# Doors_lighting_control.net
KiCad netlist of a schematic drawn in Altium Designer
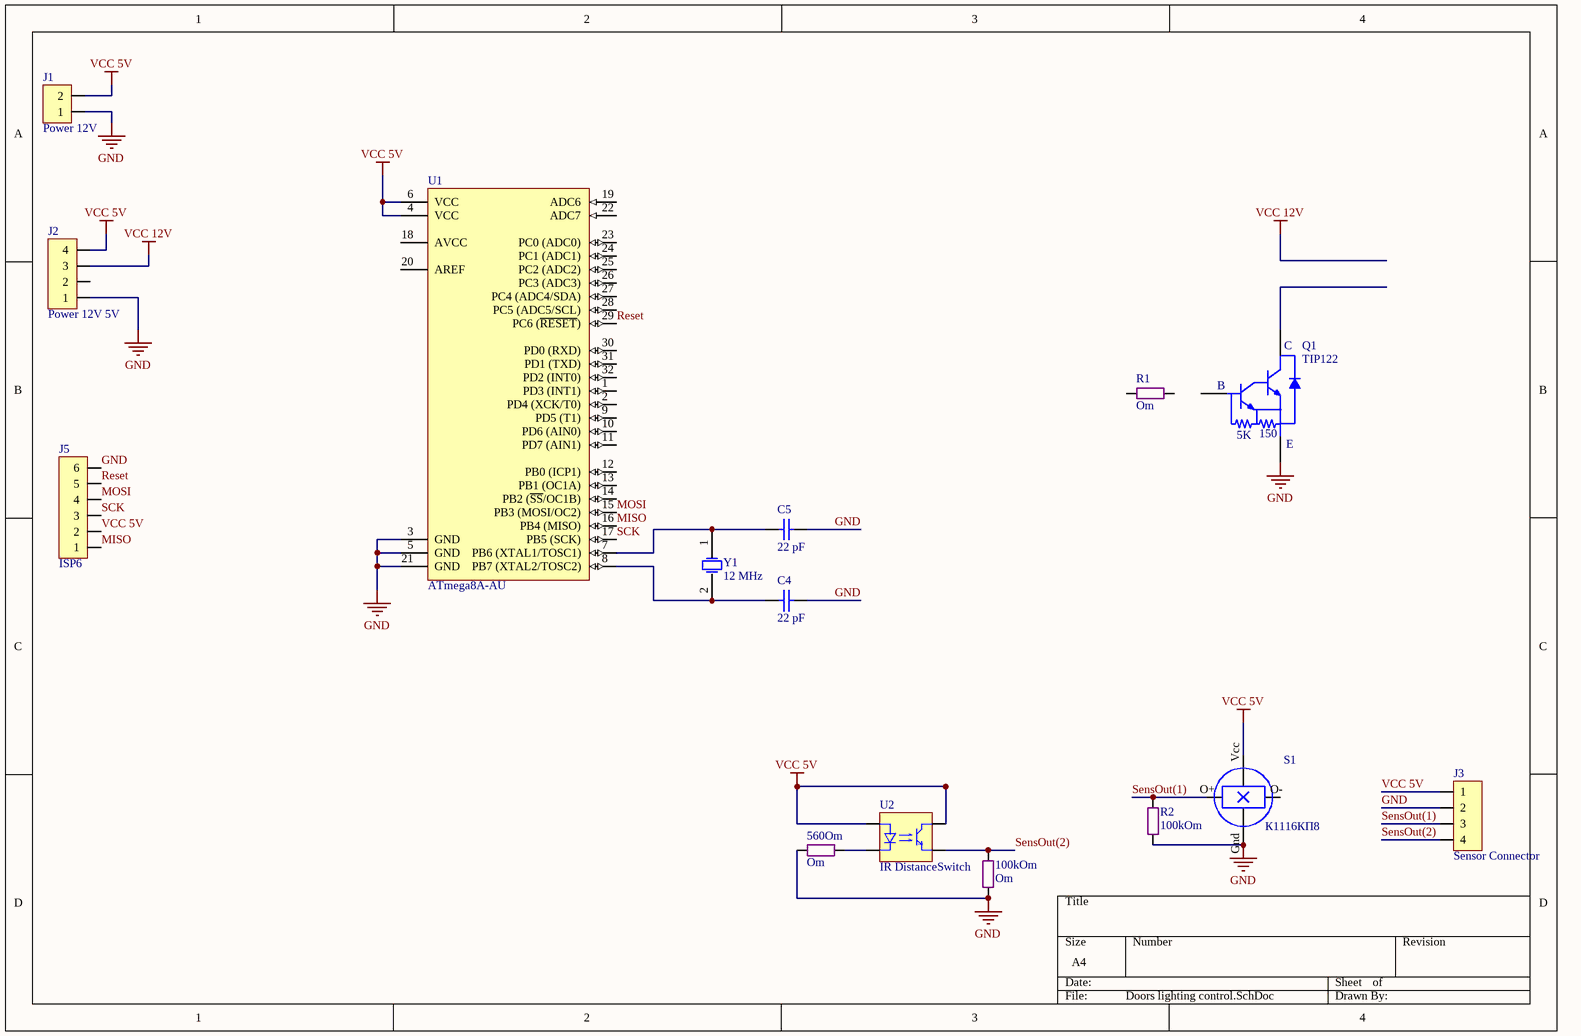
[diagram p0: Doors lighting control.SchDoc]

(export (version "E")
  (design (tool "Eeschema 10.0.6"))
  (components
    (comp (ref "100kOm")
      (value "Om")
      (footprint "PassiveComponents:SMD 0805 (2012)")
      (libsource (lib "PassiveComponents") (part "Res All Types"))
    )
    (comp (ref "560Om")
      (value "Om")
      (footprint "PassiveComponents:SMD 0805 (2012)")
      (libsource (lib "PassiveComponents") (part "Res All Types"))
    )
    (comp (ref "C4")
      (value "22 pF")
      (footprint "Capacitor:Cap P5.08MM (3p) disk2")
      (description "Capacitor")
      (libsource (lib "Capacitor") (part "Cap Ceramic"))
    )
    (comp (ref "C5")
      (value "22 pF")
      (footprint "Capacitor:Cap P5.08MM (3p) disk2")
      (description "Capacitor")
      (libsource (lib "Capacitor") (part "Cap Ceramic"))
    )
    (comp (ref "J1")
      (value "Power 12V")
      (footprint "Connector:Molex Micro-Fit 3.0 - 2 pin D R")
      (description "Horisontal, Dbl line, Male - 3mm")
      (fields (field (name "PART NUMBER") "430450200"))
      (libsource (lib "Connector") (part "Micro-Fit 2R (1x2)"))
    )
    (comp (ref "J2")
      (value "Power 12V 5V")
      (footprint "Connector:Molex Micro-Fit 3.0 - 4 pin D R")
      (description "Horisontal, Dbl line, Male - 3mm")
      (fields (field (name "PART NUMBER") "0430450402"))
      (libsource (lib "Connector") (part "Micro-Fit 4R (2x2)"))
    )
    (comp (ref "J3")
      (value "Sensor Connector")
      (footprint "Connector:Molex Micro-Fit 3.0 - 4 pin D R")
      (description "Horisontal, Dbl line, Male - 3mm")
      (fields (field (name "PART NUMBER") "0430450402"))
      (libsource (lib "") (part "Micro-Fit 4R (2x2)_1"))
    )
    (comp (ref "J5")
      (value "ISP6")
      (footprint "Connector:LINE 2.54 x 6D (2 x 3)")
      (description "Vert, Dbl line, Male")
      (libsource (lib "Connector") (part "PLD-6 (2 x 3)"))
    )
    (comp (ref "Q1")
      (value "TIP122")
      (footprint "GeneralCases:TO220-2")
      (description "NPN Darlington 5A, 65W, 100V, h>1000")
      (libsource (lib "Transistor") (part "TIP122"))
    )
    (comp (ref "R1")
      (value "Om")
      (footprint "PassiveComponents:SMD 0805 (2012)")
      (libsource (lib "PassiveComponents") (part "Res All Types"))
    )
    (comp (ref "R2")
      (value "100kOm")
      (footprint "PassiveComponents:SMD 0805 (2012)")
      (libsource (lib "PassiveComponents") (part "Res All Types"))
    )
    (comp (ref "S1")
      (value "Hall Sens")
      (footprint "Sensors:Hall Sensor 3Pin")
      (fields (field (name "NAME") "К1116КП8"))
      (libsource (lib "Sensors") (part "Hall Sensor K1116KP8"))
    )
    (comp (ref "U1")
      (value "ATmega8A-AU")
      (footprint "32A_N")
      (fields (field (name "PUBLISHER") "Altium Limited"))
      (libsource (lib "Atmel Microcontroller 8-Bit megaAVR") (part "ATmega8A-AU"))
    )
    (comp (ref "U2")
      (value "IR DistanceSwitch")
      (footprint "LED:OptoSwitchDistance")
      (description "IR opt Distance Switch")
      (libsource (lib "Transistor") (part "Optocouplier (IR Distance Switch)"))
    )
    (comp (ref "Y1")
      (value "12 MHz")
      (footprint "PassiveComponents:XTAL - 2")
      (description "Crystal Oscillator")
      (fields (field (name "PUBLISHER") "Altium Limited"))
      (libsource (lib "PassiveComponents") (part "XTAL"))
    )
  )
  (nets
    (net (code "1") (name "/MISO") (class "Default")
      (node (ref "J5") (pin "1") (pinfunction "1_1") (pintype "passive"))
      (node (ref "U1") (pin "16") (pinfunction "PB4_(MISO)_16") (pintype "bidirectional"))
    )
    (net (code "2") (name "/MOSI") (class "Default")
      (node (ref "J5") (pin "4") (pinfunction "4_4") (pintype "passive"))
      (node (ref "U1") (pin "15") (pinfunction "PB3_(MOSI/OC2)_15") (pintype "bidirectional"))
    )
    (net (code "3") (name "/Reset") (class "Default")
      (node (ref "J5") (pin "5") (pinfunction "5_5") (pintype "passive"))
      (node (ref "U1") (pin "29") (pinfunction "PC6_(~{RESET})_29") (pintype "bidirectional"))
    )
    (net (code "4") (name "/SCK") (class "Default")
      (node (ref "J5") (pin "3") (pinfunction "3_3") (pintype "passive"))
      (node (ref "U1") (pin "17") (pinfunction "PB5_(SCK)_17") (pintype "bidirectional"))
    )
    (net (code "5") (name "/SensOut(1)") (class "Default")
      (node (ref "J3") (pin "3") (pinfunction "3_3") (pintype "passive"))
      (node (ref "R2") (pin "2") (pinfunction "2_2") (pintype "passive"))
      (node (ref "S1") (pin "O+") (pinfunction "O+_O+") (pintype "passive"))
    )
    (net (code "6") (name "/SensOut(2)") (class "Default")
      (node (ref "100kOm") (pin "2") (pinfunction "2_2") (pintype "passive"))
      (node (ref "J3") (pin "4") (pinfunction "4_4") (pintype "passive"))
      (node (ref "U2") (pin "E") (pinfunction "E_E") (pintype "passive"))
    )
    (net (code "7") (name "GND") (class "Default")
      (node (ref "100kOm") (pin "1") (pinfunction "1_1") (pintype "passive"))
      (node (ref "560Om") (pin "2") (pinfunction "2_2") (pintype "passive"))
      (node (ref "C4") (pin "1") (pinfunction "1_1") (pintype "passive"))
      (node (ref "C5") (pin "1") (pinfunction "1_1") (pintype "passive"))
      (node (ref "J1") (pin "1") (pinfunction "1_1") (pintype "passive"))
      (node (ref "J2") (pin "1") (pinfunction "1_1") (pintype "passive"))
      (node (ref "J3") (pin "2") (pinfunction "2_2") (pintype "passive"))
      (node (ref "J5") (pin "6") (pinfunction "6_6") (pintype "passive"))
      (node (ref "Q1") (pin "3") (pinfunction "E_3") (pintype "passive"))
      (node (ref "R2") (pin "1") (pinfunction "1_1") (pintype "passive"))
      (node (ref "S1") (pin "Gnd") (pinfunction "Gnd_Gnd") (pintype "passive"))
      (node (ref "U1") (pin "21") (pinfunction "GND_21") (pintype "power_in"))
      (node (ref "U1") (pin "3") (pinfunction "GND_3") (pintype "power_in"))
      (node (ref "U1") (pin "5") (pinfunction "GND_5") (pintype "power_in"))
    )
    (net (code "8") (name "Net-(560Om-Pad1)") (class "Default")
      (node (ref "560Om") (pin "1") (pinfunction "1_1") (pintype "passive"))
      (node (ref "U2") (pin "K") (pinfunction "K_K") (pintype "passive"))
    )
    (net (code "9") (name "Net-(U1-PB6_(XTAL1{slash}TOSC1))") (class "Default")
      (node (ref "C5") (pin "2") (pinfunction "2_2") (pintype "passive"))
      (node (ref "U1") (pin "7") (pinfunction "PB6_(XTAL1/TOSC1)_7") (pintype "bidirectional"))
      (node (ref "Y1") (pin "1") (pinfunction "OSC1_1") (pintype "passive"))
    )
    (net (code "10") (name "Net-(U1-PB7_(XTAL2{slash}TOSC2))") (class "Default")
      (node (ref "C4") (pin "2") (pinfunction "2_2") (pintype "passive"))
      (node (ref "U1") (pin "8") (pinfunction "PB7_(XTAL2/TOSC2)_8") (pintype "bidirectional"))
      (node (ref "Y1") (pin "2") (pinfunction "OSC2_2") (pintype "passive"))
    )
    (net (code "11") (name "VCC 5V") (class "Default")
      (node (ref "J1") (pin "2") (pinfunction "2_2") (pintype "passive"))
      (node (ref "J2") (pin "4") (pinfunction "4_4") (pintype "passive"))
      (node (ref "J3") (pin "1") (pinfunction "1_1") (pintype "passive"))
      (node (ref "J5") (pin "2") (pinfunction "2_2") (pintype "passive"))
      (node (ref "S1") (pin "Vcc") (pinfunction "Vcc_Vcc") (pintype "passive"))
      (node (ref "U1") (pin "4") (pinfunction "VCC_4") (pintype "power_in"))
      (node (ref "U1") (pin "6") (pinfunction "VCC_6") (pintype "power_in"))
      (node (ref "U2") (pin "A") (pinfunction "A_A") (pintype "passive"))
      (node (ref "U2") (pin "C") (pinfunction "C_C") (pintype "passive"))
    )
    (net (code "12") (name "VCC 12V") (class "Default")
      (node (ref "J2") (pin "3") (pinfunction "3_3") (pintype "passive"))
    )
    (net (code "13") (name "unconnected-(J2-Pad2)") (class "Default")
      (node (ref "J2") (pin "2") (pinfunction "2_2") (pintype "passive"))
    )
    (net (code "14") (name "unconnected-(Q1-B-Pad1)") (class "Default")
      (node (ref "Q1") (pin "1") (pinfunction "B_1") (pintype "passive"))
    )
    (net (code "15") (name "unconnected-(Q1-C-Pad2)") (class "Default")
      (node (ref "Q1") (pin "2") (pinfunction "C_2") (pintype "passive"))
    )
    (net (code "16") (name "unconnected-(R1-Pad1)") (class "Default")
      (node (ref "R1") (pin "1") (pinfunction "1_1") (pintype "passive"))
    )
    (net (code "17") (name "unconnected-(R1-Pad2)") (class "Default")
      (node (ref "R1") (pin "2") (pinfunction "2_2") (pintype "passive"))
    )
    (net (code "18") (name "unconnected-(S1-PadO-)") (class "Default")
      (node (ref "S1") (pin "O-") (pinfunction "O-_O-") (pintype "passive"))
    )
    (net (code "19") (name "unconnected-(U1-ADC6-Pad19)") (class "Default")
      (node (ref "U1") (pin "19") (pinfunction "ADC6_19") (pintype "input"))
    )
    (net (code "20") (name "unconnected-(U1-ADC7-Pad22)") (class "Default")
      (node (ref "U1") (pin "22") (pinfunction "ADC7_22") (pintype "input"))
    )
    (net (code "21") (name "unconnected-(U1-AREF-Pad20)") (class "Default")
      (node (ref "U1") (pin "20") (pinfunction "AREF_20") (pintype "power_in"))
    )
    (net (code "22") (name "unconnected-(U1-AVCC-Pad18)") (class "Default")
      (node (ref "U1") (pin "18") (pinfunction "AVCC_18") (pintype "power_in"))
    )
    (net (code "23") (name "unconnected-(U1-PB0_(ICP1)-Pad12)") (class "Default")
      (node (ref "U1") (pin "12") (pinfunction "PB0_(ICP1)_12") (pintype "bidirectional"))
    )
    (net (code "24") (name "unconnected-(U1-PB1_(OC1A)-Pad13)") (class "Default")
      (node (ref "U1") (pin "13") (pinfunction "PB1_(OC1A)_13") (pintype "bidirectional"))
    )
    (net (code "25") (name "unconnected-(U1-PB2_(~{SS}{slash}OC1B)-Pad14)") (class "Default")
      (node (ref "U1") (pin "14") (pinfunction "PB2_(~{SS}/OC1B)_14") (pintype "bidirectional"))
    )
    (net (code "26") (name "unconnected-(U1-PC0_(ADC0)-Pad23)") (class "Default")
      (node (ref "U1") (pin "23") (pinfunction "PC0_(ADC0)_23") (pintype "bidirectional"))
    )
    (net (code "27") (name "unconnected-(U1-PC1_(ADC1)-Pad24)") (class "Default")
      (node (ref "U1") (pin "24") (pinfunction "PC1_(ADC1)_24") (pintype "bidirectional"))
    )
    (net (code "28") (name "unconnected-(U1-PC2_(ADC2)-Pad25)") (class "Default")
      (node (ref "U1") (pin "25") (pinfunction "PC2_(ADC2)_25") (pintype "bidirectional"))
    )
    (net (code "29") (name "unconnected-(U1-PC3_(ADC3)-Pad26)") (class "Default")
      (node (ref "U1") (pin "26") (pinfunction "PC3_(ADC3)_26") (pintype "bidirectional"))
    )
    (net (code "30") (name "unconnected-(U1-PC4_(ADC4{slash}SDA)-Pad27)") (class "Default")
      (node (ref "U1") (pin "27") (pinfunction "PC4_(ADC4/SDA)_27") (pintype "bidirectional"))
    )
    (net (code "31") (name "unconnected-(U1-PC5_(ADC5{slash}SCL)-Pad28)") (class "Default")
      (node (ref "U1") (pin "28") (pinfunction "PC5_(ADC5/SCL)_28") (pintype "bidirectional"))
    )
    (net (code "32") (name "unconnected-(U1-PD0_(RXD)-Pad30)") (class "Default")
      (node (ref "U1") (pin "30") (pinfunction "PD0_(RXD)_30") (pintype "bidirectional"))
    )
    (net (code "33") (name "unconnected-(U1-PD1_(TXD)-Pad31)") (class "Default")
      (node (ref "U1") (pin "31") (pinfunction "PD1_(TXD)_31") (pintype "bidirectional"))
    )
    (net (code "34") (name "unconnected-(U1-PD2_(INT0)-Pad32)") (class "Default")
      (node (ref "U1") (pin "32") (pinfunction "PD2_(INT0)_32") (pintype "bidirectional"))
    )
    (net (code "35") (name "unconnected-(U1-PD3_(INT1)-Pad1)") (class "Default")
      (node (ref "U1") (pin "1") (pinfunction "PD3_(INT1)_1") (pintype "bidirectional"))
    )
    (net (code "36") (name "unconnected-(U1-PD4_(XCK{slash}T0)-Pad2)") (class "Default")
      (node (ref "U1") (pin "2") (pinfunction "PD4_(XCK/T0)_2") (pintype "bidirectional"))
    )
    (net (code "37") (name "unconnected-(U1-PD5_(T1)-Pad9)") (class "Default")
      (node (ref "U1") (pin "9") (pinfunction "PD5_(T1)_9") (pintype "bidirectional"))
    )
    (net (code "38") (name "unconnected-(U1-PD6_(AIN0)-Pad10)") (class "Default")
      (node (ref "U1") (pin "10") (pinfunction "PD6_(AIN0)_10") (pintype "bidirectional"))
    )
    (net (code "39") (name "unconnected-(U1-PD7_(AIN1)-Pad11)") (class "Default")
      (node (ref "U1") (pin "11") (pinfunction "PD7_(AIN1)_11") (pintype "bidirectional"))
    )
  )
)
